# product.net
KiCad netlist of a schematic drawn in EAGLE
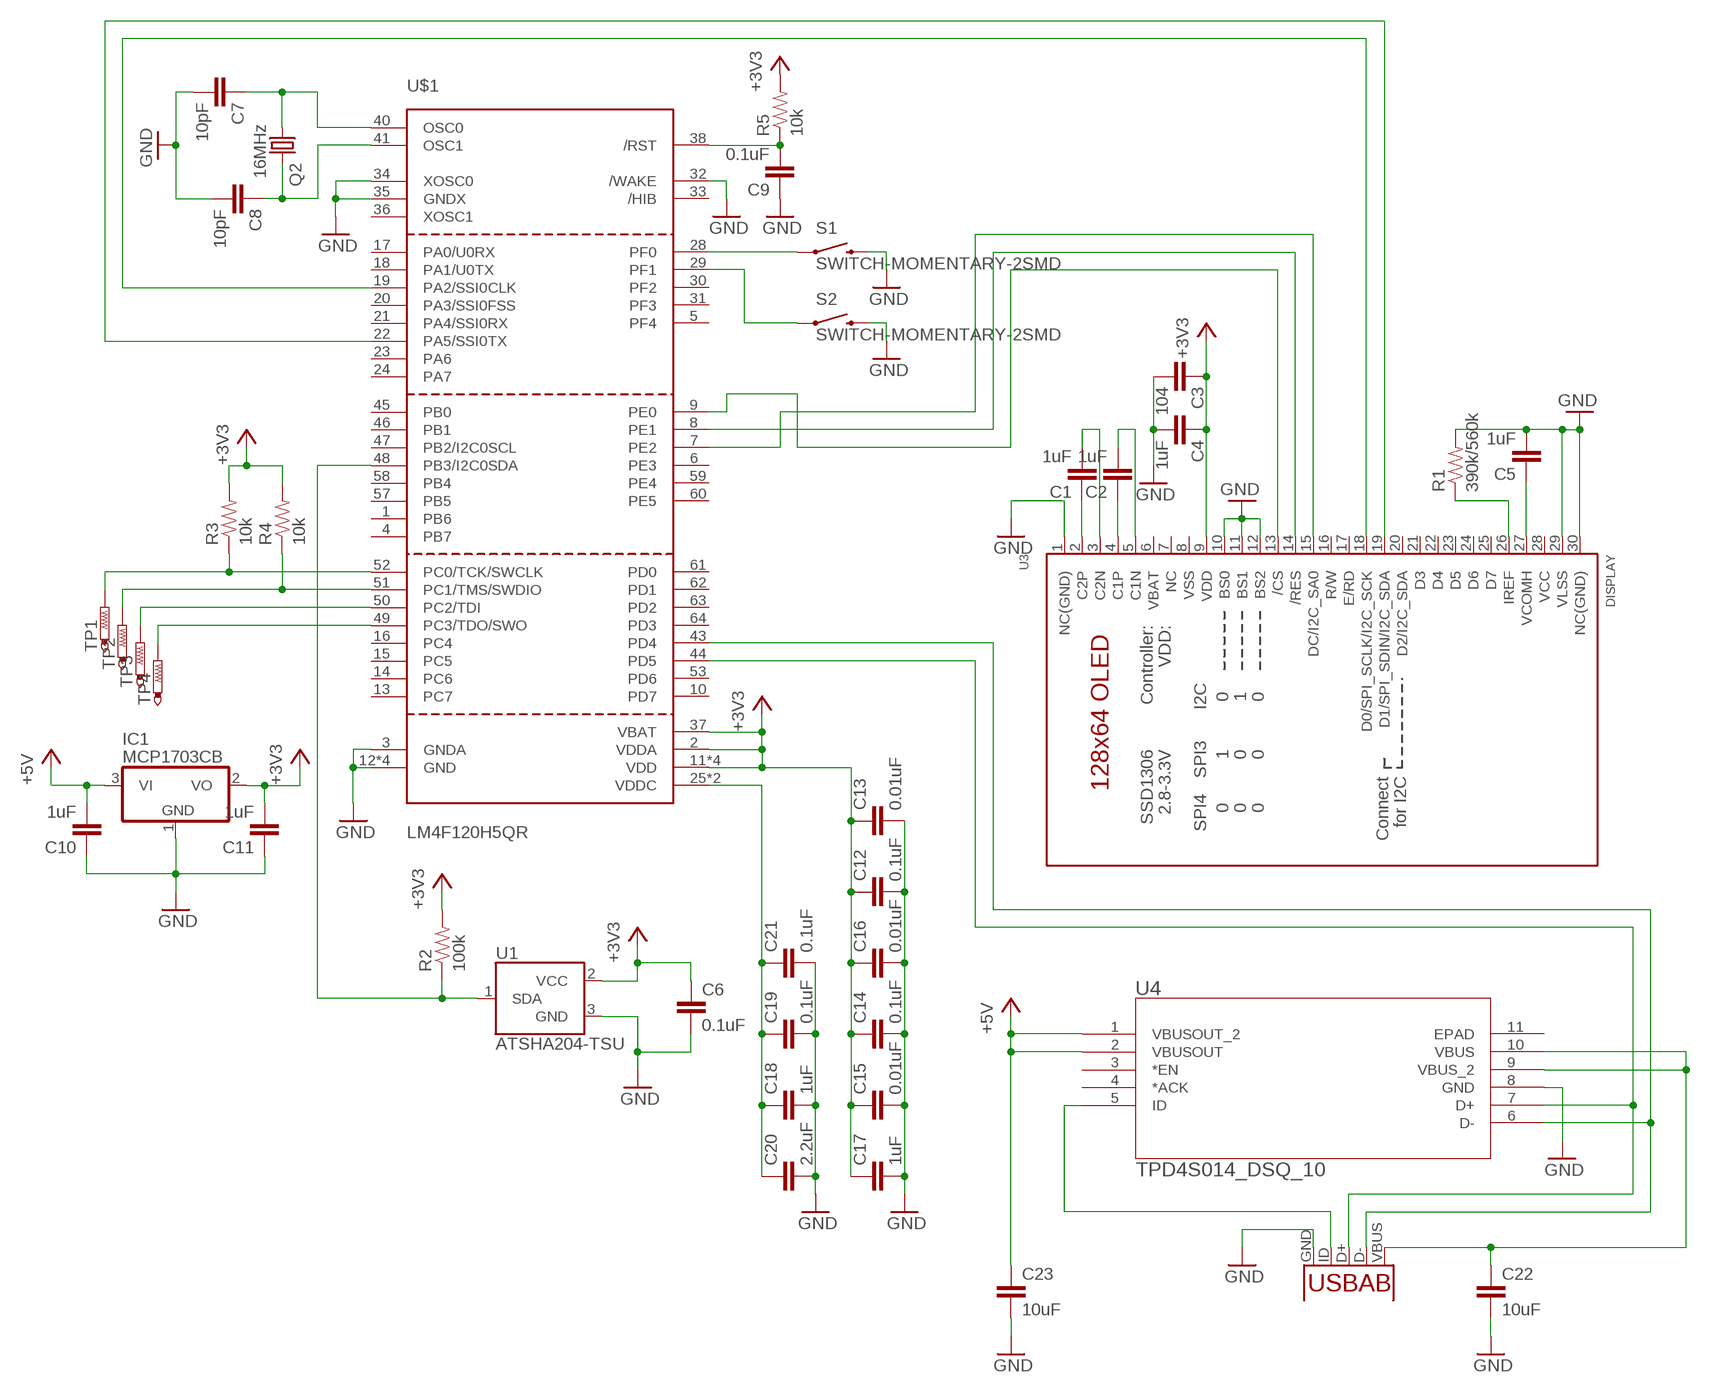
[diagram p0: schematic, sheet 1]

(export (version "E")
  (design (tool "Eeschema 10.0.6"))
  (components
    (comp (ref "C1")
      (value "1uF")
      (footprint "eagle-import:0402-CAP")
      (libsource (lib "eagle-import") (part "CAP0402-CAP"))
    )
    (comp (ref "C2")
      (value "1uF")
      (footprint "eagle-import:0402-CAP")
      (libsource (lib "eagle-import") (part "CAP0402-CAP"))
    )
    (comp (ref "C3")
      (value "104")
      (footprint "eagle-import:0402-CAP")
      (libsource (lib "eagle-import") (part "CAP0402-CAP"))
    )
    (comp (ref "C4")
      (value "1uF")
      (footprint "eagle-import:0402-CAP")
      (libsource (lib "eagle-import") (part "CAP0402-CAP"))
    )
    (comp (ref "C5")
      (value "1uF")
      (footprint "eagle-import:0402-CAP")
      (libsource (lib "eagle-import") (part "CAP0402-CAP"))
    )
    (comp (ref "C6")
      (value "0.1uF")
      (footprint "eagle-import:0402-CAP")
      (libsource (lib "eagle-import") (part "CAP0402-CAP"))
    )
    (comp (ref "C7")
      (value "10pF")
      (footprint "eagle-import:0402-CAP")
      (libsource (lib "eagle-import") (part "CAP0402-CAP"))
    )
    (comp (ref "C8")
      (value "10pF")
      (footprint "eagle-import:0402-CAP")
      (libsource (lib "eagle-import") (part "CAP0402-CAP"))
    )
    (comp (ref "C9")
      (value "0.1uF")
      (footprint "eagle-import:0402-CAP")
      (libsource (lib "eagle-import") (part "CAP0402-CAP"))
    )
    (comp (ref "C10")
      (value "1uF")
      (footprint "eagle-import:0402-CAP")
      (libsource (lib "eagle-import") (part "CAP0402-CAP"))
    )
    (comp (ref "C11")
      (value "1uF")
      (footprint "eagle-import:0402-CAP")
      (libsource (lib "eagle-import") (part "CAP0402-CAP"))
    )
    (comp (ref "C12")
      (value "0.1uF")
      (footprint "eagle-import:0402-CAP")
      (libsource (lib "eagle-import") (part "CAP0402-CAP"))
    )
    (comp (ref "C13")
      (value "0.01uF")
      (footprint "eagle-import:0402-CAP")
      (libsource (lib "eagle-import") (part "CAP0402-CAP"))
    )
    (comp (ref "C14")
      (value "0.1uF")
      (footprint "eagle-import:0402-CAP")
      (libsource (lib "eagle-import") (part "CAP0402-CAP"))
    )
    (comp (ref "C15")
      (value "0.01uF")
      (footprint "eagle-import:0402-CAP")
      (libsource (lib "eagle-import") (part "CAP0402-CAP"))
    )
    (comp (ref "C16")
      (value "0.01uF")
      (footprint "eagle-import:0402-CAP")
      (libsource (lib "eagle-import") (part "CAP0402-CAP"))
    )
    (comp (ref "C17")
      (value "1uF")
      (footprint "eagle-import:0402-CAP")
      (libsource (lib "eagle-import") (part "CAP0402-CAP"))
    )
    (comp (ref "C18")
      (value "1uF")
      (footprint "eagle-import:0402-CAP")
      (libsource (lib "eagle-import") (part "CAP0402-CAP"))
    )
    (comp (ref "C19")
      (value "0.1uF")
      (footprint "eagle-import:0402-CAP")
      (libsource (lib "eagle-import") (part "CAP0402-CAP"))
    )
    (comp (ref "C20")
      (value "2.2uF")
      (footprint "eagle-import:0402-CAP")
      (libsource (lib "eagle-import") (part "CAP0402-CAP"))
    )
    (comp (ref "C21")
      (value "0.1uF")
      (footprint "eagle-import:0402-CAP")
      (libsource (lib "eagle-import") (part "CAP0402-CAP"))
    )
    (comp (ref "C22")
      (value "10uF")
      (footprint "eagle-import:0402-CAP")
      (libsource (lib "eagle-import") (part "CAP0402-CAP"))
    )
    (comp (ref "C23")
      (value "10uF")
      (footprint "eagle-import:0402-CAP")
      (libsource (lib "eagle-import") (part "CAP0402-CAP"))
    )
    (comp (ref "IC1")
      (value "MCP1703CB")
      (footprint "eagle-import:SOT23")
      (libsource (lib "eagle-import") (part "MCP1703CB"))
    )
    (comp (ref "Q2")
      (value "16MHz")
      (footprint "eagle-import:CTS406")
      (libsource (lib "eagle-import") (part "CRYSTALCTS406"))
    )
    (comp (ref "R1")
      (value "390k/560k")
      (footprint "eagle-import:0402-RES")
      (libsource (lib "eagle-import") (part "RESISTOR0402-RES"))
    )
    (comp (ref "R2")
      (value "100k")
      (footprint "eagle-import:0402-RES")
      (libsource (lib "eagle-import") (part "RESISTOR0402-RES"))
    )
    (comp (ref "R3")
      (value "10k")
      (footprint "eagle-import:0402-RES")
      (libsource (lib "eagle-import") (part "RESISTOR0402-RES"))
    )
    (comp (ref "R4")
      (value "10k")
      (footprint "eagle-import:0402-RES")
      (libsource (lib "eagle-import") (part "RESISTOR0402-RES"))
    )
    (comp (ref "R5")
      (value "10k")
      (footprint "eagle-import:0402-RES")
      (libsource (lib "eagle-import") (part "RESISTOR0402-RES"))
    )
    (comp (ref "S1")
      (value "SWITCH-MOMENTARY-2SMD")
      (footprint "eagle-import:TACTILE_SWITCH_SMD")
      (libsource (lib "eagle-import") (part "SWITCH-MOMENTARY-2SMD"))
    )
    (comp (ref "S2")
      (value "SWITCH-MOMENTARY-2SMD")
      (footprint "eagle-import:TACTILE_SWITCH_SMD")
      (libsource (lib "eagle-import") (part "SWITCH-MOMENTARY-2SMD"))
    )
    (comp (ref "TP1")
      (value "PTR1TP10R")
      (footprint "eagle-import:TP10R")
      (libsource (lib "eagle-import") (part "PTR1TP10R"))
    )
    (comp (ref "TP2")
      (value "PTR1TP10R")
      (footprint "eagle-import:TP10R")
      (libsource (lib "eagle-import") (part "PTR1TP10R"))
    )
    (comp (ref "TP3")
      (value "PTR1TP10R")
      (footprint "eagle-import:TP10R")
      (libsource (lib "eagle-import") (part "PTR1TP10R"))
    )
    (comp (ref "TP4")
      (value "PTR1TP10R")
      (footprint "eagle-import:TP10R")
      (libsource (lib "eagle-import") (part "PTR1TP10R"))
    )
    (comp (ref "U$1")
      (value "LM4F120H5QR")
      (footprint "eagle-import:LQFP64")
      (libsource (lib "eagle-import") (part "LM4F120H5QR"))
    )
    (comp (ref "U1")
      (value "ATSHA204-TSU")
      (footprint "eagle-import:SOT23-3")
      (libsource (lib "eagle-import") (part "ATSHA204-TSU"))
    )
    (comp (ref "U2")
      (value "USB")
      (footprint "eagle-import:USB-AB-MICRO-SMD")
      (libsource (lib "eagle-import") (part "USB-AB"))
    )
    (comp (ref "U3")
      (value "DISPLAY")
      (footprint "eagle-import:UG-2864HSWEG01_0.96IN_WRAPAROUND")
      (libsource (lib "eagle-import") (part "DISP_OLED_UG-2864HSWEG010.96{dblquote}"))
    )
    (comp (ref "U4")
      (value "TPD4S014_DSQ_10")
      (footprint "eagle-import:DSQ10_1P5X0P9")
      (libsource (lib "eagle-import") (part "TPD4S014_DSQ_10"))
    )
  )
  (nets
    (net (code "1") (name "+3V3") (class "Default")
      (node (ref "C11") (pin "2") (pinfunction "2_2") (pintype "passive"))
      (node (ref "C12") (pin "1") (pinfunction "1_1") (pintype "passive"))
      (node (ref "C13") (pin "1") (pinfunction "1_1") (pintype "passive"))
      (node (ref "C14") (pin "1") (pinfunction "1_1") (pintype "passive"))
      (node (ref "C15") (pin "1") (pinfunction "1_1") (pintype "passive"))
      (node (ref "C16") (pin "1") (pinfunction "1_1") (pintype "passive"))
      (node (ref "C17") (pin "1") (pinfunction "1_1") (pintype "passive"))
      (node (ref "C3") (pin "1") (pinfunction "1_1") (pintype "passive"))
      (node (ref "C4") (pin "1") (pinfunction "1_1") (pintype "passive"))
      (node (ref "C6") (pin "1") (pinfunction "1_1") (pintype "passive"))
      (node (ref "IC1") (pin "2") (pinfunction "VO_2") (pintype "passive"))
      (node (ref "R2") (pin "2") (pinfunction "2_2") (pintype "passive"))
      (node (ref "R3") (pin "2") (pinfunction "2_2") (pintype "passive"))
      (node (ref "R4") (pin "2") (pinfunction "2_2") (pintype "passive"))
      (node (ref "R5") (pin "2") (pinfunction "2_2") (pintype "passive"))
      (node (ref "U$1") (pin "11") (pinfunction "VDD_11") (pintype "power_in"))
      (node (ref "U$1") (pin "2") (pinfunction "VDDA_2") (pintype "power_in"))
      (node (ref "U$1") (pin "26") (pinfunction "VDD_26") (pintype "power_in"))
      (node (ref "U$1") (pin "37") (pinfunction "VBAT_37") (pintype "power_in"))
      (node (ref "U$1") (pin "42") (pinfunction "VDD_42") (pintype "power_in"))
      (node (ref "U$1") (pin "54") (pinfunction "VDD_54") (pintype "power_in"))
      (node (ref "U1") (pin "2") (pinfunction "VCC_2") (pintype "bidirectional"))
      (node (ref "U3") (pin "9") (pinfunction "VDD_9") (pintype "power_in"))
    )
    (net (code "2") (name "+5V") (class "Default")
      (node (ref "C10") (pin "2") (pinfunction "2_2") (pintype "passive"))
      (node (ref "C23") (pin "1") (pinfunction "1_1") (pintype "passive"))
      (node (ref "IC1") (pin "3") (pinfunction "VI_3") (pintype "input"))
      (node (ref "U4") (pin "1") (pinfunction "VBUSOUT_2_1") (pintype "passive"))
      (node (ref "U4") (pin "2") (pinfunction "VBUSOUT_2") (pintype "passive"))
    )
    (net (code "3") (name "/VCC") (class "Default")
      (node (ref "U3") (pin "28") (pinfunction "VCC_28") (pintype "power_in"))
    )
    (net (code "4") (name "/VSS") (class "Default")
      (node (ref "U3") (pin "8") (pinfunction "VSS_8") (pintype "power_in"))
    )
    (net (code "5") (name "GND") (class "Default")
      (node (ref "C10") (pin "1") (pinfunction "1_1") (pintype "passive"))
      (node (ref "C11") (pin "1") (pinfunction "1_1") (pintype "passive"))
      (node (ref "C12") (pin "2") (pinfunction "2_2") (pintype "passive"))
      (node (ref "C13") (pin "2") (pinfunction "2_2") (pintype "passive"))
      (node (ref "C14") (pin "2") (pinfunction "2_2") (pintype "passive"))
      (node (ref "C15") (pin "2") (pinfunction "2_2") (pintype "passive"))
      (node (ref "C16") (pin "2") (pinfunction "2_2") (pintype "passive"))
      (node (ref "C17") (pin "2") (pinfunction "2_2") (pintype "passive"))
      (node (ref "C18") (pin "2") (pinfunction "2_2") (pintype "passive"))
      (node (ref "C19") (pin "2") (pinfunction "2_2") (pintype "passive"))
      (node (ref "C20") (pin "2") (pinfunction "2_2") (pintype "passive"))
      (node (ref "C21") (pin "2") (pinfunction "2_2") (pintype "passive"))
      (node (ref "C22") (pin "2") (pinfunction "2_2") (pintype "passive"))
      (node (ref "C23") (pin "2") (pinfunction "2_2") (pintype "passive"))
      (node (ref "C3") (pin "2") (pinfunction "2_2") (pintype "passive"))
      (node (ref "C4") (pin "2") (pinfunction "2_2") (pintype "passive"))
      (node (ref "C5") (pin "2") (pinfunction "2_2") (pintype "passive"))
      (node (ref "C6") (pin "2") (pinfunction "2_2") (pintype "passive"))
      (node (ref "C7") (pin "2") (pinfunction "2_2") (pintype "passive"))
      (node (ref "C8") (pin "2") (pinfunction "2_2") (pintype "passive"))
      (node (ref "C9") (pin "1") (pinfunction "1_1") (pintype "passive"))
      (node (ref "IC1") (pin "1") (pinfunction "GND_1") (pintype "passive"))
      (node (ref "R1") (pin "2") (pinfunction "2_2") (pintype "passive"))
      (node (ref "S1") (pin "3") (pinfunction "2_3") (pintype "passive"))
      (node (ref "S2") (pin "3") (pinfunction "2_3") (pintype "passive"))
      (node (ref "U$1") (pin "12") (pinfunction "GND_12") (pintype "power_in"))
      (node (ref "U$1") (pin "27") (pinfunction "GND_27") (pintype "power_in"))
      (node (ref "U$1") (pin "3") (pinfunction "GNDA_3") (pintype "power_in"))
      (node (ref "U$1") (pin "32") (pinfunction "/WAKE_32") (pintype "bidirectional"))
      (node (ref "U$1") (pin "34") (pinfunction "XOSC0_34") (pintype "passive"))
      (node (ref "U$1") (pin "35") (pinfunction "GNDX_35") (pintype "power_in"))
      (node (ref "U$1") (pin "39") (pinfunction "GND_39") (pintype "power_in"))
      (node (ref "U$1") (pin "55") (pinfunction "GND_55") (pintype "power_in"))
      (node (ref "U1") (pin "3") (pinfunction "GND_3") (pintype "bidirectional"))
      (node (ref "U2") (pin "GND") (pinfunction "GND_GND") (pintype "bidirectional"))
      (node (ref "U3") (pin "1") (pinfunction "NC(GND)_1") (pintype "input"))
      (node (ref "U3") (pin "10") (pinfunction "BS0_10") (pintype "input"))
      (node (ref "U3") (pin "11") (pinfunction "BS1_11") (pintype "input"))
      (node (ref "U3") (pin "12") (pinfunction "BS2_12") (pintype "input"))
      (node (ref "U3") (pin "29") (pinfunction "VLSS_29") (pintype "power_in"))
      (node (ref "U3") (pin "30") (pinfunction "NC(GND)_30") (pintype "input"))
      (node (ref "U4") (pin "8") (pinfunction "GND_8") (pintype "passive"))
    )
    (net (code "6") (name "Net-(C18-Pad1)") (class "Default")
      (node (ref "C18") (pin "1") (pinfunction "1_1") (pintype "passive"))
      (node (ref "C19") (pin "1") (pinfunction "1_1") (pintype "passive"))
      (node (ref "C20") (pin "1") (pinfunction "1_1") (pintype "passive"))
      (node (ref "C21") (pin "1") (pinfunction "1_1") (pintype "passive"))
      (node (ref "U$1") (pin "25") (pinfunction "VDDC_25") (pintype "power_in"))
      (node (ref "U$1") (pin "56") (pinfunction "VDDC_56") (pintype "power_in"))
    )
    (net (code "7") (name "Net-(Q2-2)") (class "Default")
      (node (ref "C8") (pin "1") (pinfunction "1_1") (pintype "passive"))
      (node (ref "Q2") (pin "3") (pinfunction "2_3") (pintype "passive"))
      (node (ref "U$1") (pin "41") (pinfunction "OSC1_41") (pintype "passive"))
    )
    (net (code "8") (name "Net-(U$1-OSC0)") (class "Default")
      (node (ref "C7") (pin "1") (pinfunction "1_1") (pintype "passive"))
      (node (ref "Q2") (pin "1") (pinfunction "1_1") (pintype "passive"))
      (node (ref "U$1") (pin "40") (pinfunction "OSC0_40") (pintype "passive"))
    )
    (net (code "9") (name "Net-(U$1-PA2{slash}SSI0CLK)") (class "Default")
      (node (ref "U$1") (pin "19") (pinfunction "PA2/SSI0CLK_19") (pintype "bidirectional"))
      (node (ref "U3") (pin "18") (pinfunction "D0/SPI_SCLK/I2C_SCK_18") (pintype "bidirectional"))
    )
    (net (code "10") (name "Net-(U$1-PA5{slash}SSI0TX)") (class "Default")
      (node (ref "U$1") (pin "22") (pinfunction "PA5/SSI0TX_22") (pintype "bidirectional"))
      (node (ref "U3") (pin "19") (pinfunction "D1/SPI_SDIN/I2C_SDA_19") (pintype "bidirectional"))
    )
    (net (code "11") (name "Net-(U$1-PB3{slash}I2C0SDA)") (class "Default")
      (node (ref "R2") (pin "1") (pinfunction "1_1") (pintype "passive"))
      (node (ref "U$1") (pin "48") (pinfunction "PB3/I2C0SDA_48") (pintype "bidirectional"))
      (node (ref "U1") (pin "1") (pinfunction "SDA_1") (pintype "bidirectional"))
    )
    (net (code "12") (name "Net-(U$1-PC0{slash}TCK{slash}SWCLK)") (class "Default")
      (node (ref "R3") (pin "1") (pinfunction "1_1") (pintype "passive"))
      (node (ref "TP1") (pin "TP") (pinfunction "TP_TP") (pintype "input"))
      (node (ref "U$1") (pin "52") (pinfunction "PC0/TCK/SWCLK_52") (pintype "bidirectional"))
    )
    (net (code "13") (name "Net-(U$1-PC1{slash}TMS{slash}SWDIO)") (class "Default")
      (node (ref "R4") (pin "1") (pinfunction "1_1") (pintype "passive"))
      (node (ref "TP2") (pin "TP") (pinfunction "TP_TP") (pintype "input"))
      (node (ref "U$1") (pin "51") (pinfunction "PC1/TMS/SWDIO_51") (pintype "bidirectional"))
    )
    (net (code "14") (name "Net-(U$1-PC2{slash}TDI)") (class "Default")
      (node (ref "TP3") (pin "TP") (pinfunction "TP_TP") (pintype "input"))
      (node (ref "U$1") (pin "50") (pinfunction "PC2/TDI_50") (pintype "bidirectional"))
    )
    (net (code "15") (name "Net-(U$1-PC3{slash}TDO{slash}SWO)") (class "Default")
      (node (ref "TP4") (pin "TP") (pinfunction "TP_TP") (pintype "input"))
      (node (ref "U$1") (pin "49") (pinfunction "PC3/TDO/SWO_49") (pintype "bidirectional"))
    )
    (net (code "16") (name "Net-(U$1-PD4)") (class "Default")
      (node (ref "U$1") (pin "43") (pinfunction "PD4_43") (pintype "bidirectional"))
      (node (ref "U2") (pin "D-") (pinfunction "D-_D-") (pintype "bidirectional"))
      (node (ref "U4") (pin "6") (pinfunction "D-_6") (pintype "passive"))
    )
    (net (code "17") (name "Net-(U$1-PD5)") (class "Default")
      (node (ref "U$1") (pin "44") (pinfunction "PD5_44") (pintype "bidirectional"))
      (node (ref "U2") (pin "D+") (pinfunction "D+_D+") (pintype "bidirectional"))
      (node (ref "U4") (pin "7") (pinfunction "D+_7") (pintype "passive"))
    )
    (net (code "18") (name "Net-(U$1-PE0)") (class "Default")
      (node (ref "U$1") (pin "9") (pinfunction "PE0_9") (pintype "bidirectional"))
      (node (ref "U3") (pin "13") (pinfunction "/CS_13") (pintype "input"))
    )
    (net (code "19") (name "Net-(U$1-PE1)") (class "Default")
      (node (ref "U$1") (pin "8") (pinfunction "PE1_8") (pintype "bidirectional"))
      (node (ref "U3") (pin "14") (pinfunction "/RES_14") (pintype "input"))
    )
    (net (code "20") (name "Net-(U$1-PE2)") (class "Default")
      (node (ref "U$1") (pin "7") (pinfunction "PE2_7") (pintype "bidirectional"))
      (node (ref "U3") (pin "15") (pinfunction "DC/I2C_SA0_15") (pintype "input"))
    )
    (net (code "21") (name "Net-(U$1-PF0)") (class "Default")
      (node (ref "S1") (pin "1") (pinfunction "1_1") (pintype "passive"))
      (node (ref "U$1") (pin "28") (pinfunction "PF0_28") (pintype "bidirectional"))
    )
    (net (code "22") (name "Net-(U$1-PF1)") (class "Default")
      (node (ref "S2") (pin "1") (pinfunction "1_1") (pintype "passive"))
      (node (ref "U$1") (pin "29") (pinfunction "PF1_29") (pintype "bidirectional"))
    )
    (net (code "23") (name "Net-(U$1-{slash}RST)") (class "Default")
      (node (ref "C9") (pin "2") (pinfunction "2_2") (pintype "passive"))
      (node (ref "R5") (pin "1") (pinfunction "1_1") (pintype "passive"))
      (node (ref "U$1") (pin "38") (pinfunction "/RST_38") (pintype "bidirectional"))
    )
    (net (code "24") (name "Net-(U2-USBID)") (class "Default")
      (node (ref "U2") (pin "ID") (pinfunction "USBID_ID") (pintype "bidirectional"))
      (node (ref "U4") (pin "5") (pinfunction "ID_5") (pintype "passive"))
    )
    (net (code "25") (name "Net-(U3-C1N)") (class "Default")
      (node (ref "C2") (pin "2") (pinfunction "2_2") (pintype "passive"))
      (node (ref "U3") (pin "5") (pinfunction "C1N_5") (pintype "input"))
    )
    (net (code "26") (name "Net-(U3-C1P)") (class "Default")
      (node (ref "C2") (pin "1") (pinfunction "1_1") (pintype "passive"))
      (node (ref "U3") (pin "4") (pinfunction "C1P_4") (pintype "input"))
    )
    (net (code "27") (name "Net-(U3-C2N)") (class "Default")
      (node (ref "C1") (pin "2") (pinfunction "2_2") (pintype "passive"))
      (node (ref "U3") (pin "3") (pinfunction "C2N_3") (pintype "input"))
    )
    (net (code "28") (name "Net-(U3-C2P)") (class "Default")
      (node (ref "C1") (pin "1") (pinfunction "1_1") (pintype "passive"))
      (node (ref "U3") (pin "2") (pinfunction "C2P_2") (pintype "input"))
    )
    (net (code "29") (name "Net-(U3-IREF)") (class "Default")
      (node (ref "R1") (pin "1") (pinfunction "1_1") (pintype "passive"))
      (node (ref "U3") (pin "26") (pinfunction "IREF_26") (pintype "input"))
    )
    (net (code "30") (name "Net-(U3-VCOMH)") (class "Default")
      (node (ref "C5") (pin "1") (pinfunction "1_1") (pintype "passive"))
      (node (ref "U3") (pin "27") (pinfunction "VCOMH_27") (pintype "output"))
    )
    (net (code "31") (name "Net-(U4-VBUS)") (class "Default")
      (node (ref "C22") (pin "1") (pinfunction "1_1") (pintype "passive"))
      (node (ref "U2") (pin "VBUS") (pinfunction "VBUS_VBUS") (pintype "bidirectional"))
      (node (ref "U4") (pin "10") (pinfunction "VBUS_10") (pintype "passive"))
      (node (ref "U4") (pin "9") (pinfunction "VBUS_2_9") (pintype "passive"))
    )
    (net (code "32") (name "unconnected-(U$1-PA0{slash}U0RX-Pad17)") (class "Default")
      (node (ref "U$1") (pin "17") (pinfunction "PA0/U0RX_17") (pintype "bidirectional"))
    )
    (net (code "33") (name "unconnected-(U$1-PA1{slash}U0TX-Pad18)") (class "Default")
      (node (ref "U$1") (pin "18") (pinfunction "PA1/U0TX_18") (pintype "bidirectional"))
    )
    (net (code "34") (name "unconnected-(U$1-PA3{slash}SSI0FSS-Pad20)") (class "Default")
      (node (ref "U$1") (pin "20") (pinfunction "PA3/SSI0FSS_20") (pintype "bidirectional"))
    )
    (net (code "35") (name "unconnected-(U$1-PA4{slash}SSI0RX-Pad21)") (class "Default")
      (node (ref "U$1") (pin "21") (pinfunction "PA4/SSI0RX_21") (pintype "bidirectional"))
    )
    (net (code "36") (name "unconnected-(U$1-PA6-Pad23)") (class "Default")
      (node (ref "U$1") (pin "23") (pinfunction "PA6_23") (pintype "bidirectional"))
    )
    (net (code "37") (name "unconnected-(U$1-PA7-Pad24)") (class "Default")
      (node (ref "U$1") (pin "24") (pinfunction "PA7_24") (pintype "bidirectional"))
    )
    (net (code "38") (name "unconnected-(U$1-PB0-Pad45)") (class "Default")
      (node (ref "U$1") (pin "45") (pinfunction "PB0_45") (pintype "bidirectional"))
    )
    (net (code "39") (name "unconnected-(U$1-PB1-Pad46)") (class "Default")
      (node (ref "U$1") (pin "46") (pinfunction "PB1_46") (pintype "bidirectional"))
    )
    (net (code "40") (name "unconnected-(U$1-PB2{slash}I2C0SCL-Pad47)") (class "Default")
      (node (ref "U$1") (pin "47") (pinfunction "PB2/I2C0SCL_47") (pintype "bidirectional"))
    )
    (net (code "41") (name "unconnected-(U$1-PB4-Pad58)") (class "Default")
      (node (ref "U$1") (pin "58") (pinfunction "PB4_58") (pintype "bidirectional"))
    )
    (net (code "42") (name "unconnected-(U$1-PB5-Pad57)") (class "Default")
      (node (ref "U$1") (pin "57") (pinfunction "PB5_57") (pintype "bidirectional"))
    )
    (net (code "43") (name "unconnected-(U$1-PB6-Pad1)") (class "Default")
      (node (ref "U$1") (pin "1") (pinfunction "PB6_1") (pintype "bidirectional"))
    )
    (net (code "44") (name "unconnected-(U$1-PB7-Pad4)") (class "Default")
      (node (ref "U$1") (pin "4") (pinfunction "PB7_4") (pintype "bidirectional"))
    )
    (net (code "45") (name "unconnected-(U$1-PC4-Pad16)") (class "Default")
      (node (ref "U$1") (pin "16") (pinfunction "PC4_16") (pintype "bidirectional"))
    )
    (net (code "46") (name "unconnected-(U$1-PC5-Pad15)") (class "Default")
      (node (ref "U$1") (pin "15") (pinfunction "PC5_15") (pintype "bidirectional"))
    )
    (net (code "47") (name "unconnected-(U$1-PC6-Pad14)") (class "Default")
      (node (ref "U$1") (pin "14") (pinfunction "PC6_14") (pintype "bidirectional"))
    )
    (net (code "48") (name "unconnected-(U$1-PC7-Pad13)") (class "Default")
      (node (ref "U$1") (pin "13") (pinfunction "PC7_13") (pintype "bidirectional"))
    )
    (net (code "49") (name "unconnected-(U$1-PD0-Pad61)") (class "Default")
      (node (ref "U$1") (pin "61") (pinfunction "PD0_61") (pintype "bidirectional"))
    )
    (net (code "50") (name "unconnected-(U$1-PD1-Pad62)") (class "Default")
      (node (ref "U$1") (pin "62") (pinfunction "PD1_62") (pintype "bidirectional"))
    )
    (net (code "51") (name "unconnected-(U$1-PD2-Pad63)") (class "Default")
      (node (ref "U$1") (pin "63") (pinfunction "PD2_63") (pintype "bidirectional"))
    )
    (net (code "52") (name "unconnected-(U$1-PD3-Pad64)") (class "Default")
      (node (ref "U$1") (pin "64") (pinfunction "PD3_64") (pintype "bidirectional"))
    )
    (net (code "53") (name "unconnected-(U$1-PD6-Pad53)") (class "Default")
      (node (ref "U$1") (pin "53") (pinfunction "PD6_53") (pintype "bidirectional"))
    )
    (net (code "54") (name "unconnected-(U$1-PD7-Pad10)") (class "Default")
      (node (ref "U$1") (pin "10") (pinfunction "PD7_10") (pintype "bidirectional"))
    )
    (net (code "55") (name "unconnected-(U$1-PE3-Pad6)") (class "Default")
      (node (ref "U$1") (pin "6") (pinfunction "PE3_6") (pintype "bidirectional"))
    )
    (net (code "56") (name "unconnected-(U$1-PE4-Pad59)") (class "Default")
      (node (ref "U$1") (pin "59") (pinfunction "PE4_59") (pintype "bidirectional"))
    )
    (net (code "57") (name "unconnected-(U$1-PE5-Pad60)") (class "Default")
      (node (ref "U$1") (pin "60") (pinfunction "PE5_60") (pintype "bidirectional"))
    )
    (net (code "58") (name "unconnected-(U$1-PF2-Pad30)") (class "Default")
      (node (ref "U$1") (pin "30") (pinfunction "PF2_30") (pintype "bidirectional"))
    )
    (net (code "59") (name "unconnected-(U$1-PF3-Pad31)") (class "Default")
      (node (ref "U$1") (pin "31") (pinfunction "PF3_31") (pintype "bidirectional"))
    )
    (net (code "60") (name "unconnected-(U$1-PF4-Pad5)") (class "Default")
      (node (ref "U$1") (pin "5") (pinfunction "PF4_5") (pintype "bidirectional"))
    )
    (net (code "61") (name "unconnected-(U$1-XOSC1-Pad36)") (class "Default")
      (node (ref "U$1") (pin "36") (pinfunction "XOSC1_36") (pintype "passive"))
    )
    (net (code "62") (name "unconnected-(U$1-{slash}HIB-Pad33)") (class "Default")
      (node (ref "U$1") (pin "33") (pinfunction "/HIB_33") (pintype "bidirectional"))
    )
    (net (code "63") (name "unconnected-(U3-D2{slash}I2C_SDA-Pad20)") (class "Default")
      (node (ref "U3") (pin "20") (pinfunction "D2/I2C_SDA_20") (pintype "bidirectional"))
    )
    (net (code "64") (name "unconnected-(U3-D3-Pad21)") (class "Default")
      (node (ref "U3") (pin "21") (pinfunction "D3_21") (pintype "bidirectional"))
    )
    (net (code "65") (name "unconnected-(U3-D4-Pad22)") (class "Default")
      (node (ref "U3") (pin "22") (pinfunction "D4_22") (pintype "bidirectional"))
    )
    (net (code "66") (name "unconnected-(U3-D5-Pad23)") (class "Default")
      (node (ref "U3") (pin "23") (pinfunction "D5_23") (pintype "bidirectional"))
    )
    (net (code "67") (name "unconnected-(U3-D6-Pad24)") (class "Default")
      (node (ref "U3") (pin "24") (pinfunction "D6_24") (pintype "bidirectional"))
    )
    (net (code "68") (name "unconnected-(U3-D7-Pad25)") (class "Default")
      (node (ref "U3") (pin "25") (pinfunction "D7_25") (pintype "bidirectional"))
    )
    (net (code "69") (name "unconnected-(U3-E{slash}RD-Pad17)") (class "Default")
      (node (ref "U3") (pin "17") (pinfunction "E/RD_17") (pintype "input"))
    )
    (net (code "70") (name "unconnected-(U3-NC-Pad7)") (class "Default")
      (node (ref "U3") (pin "7") (pinfunction "NC_7") (pintype "no_connect"))
    )
    (net (code "71") (name "unconnected-(U3-R{slash}W-Pad16)") (class "Default")
      (node (ref "U3") (pin "16") (pinfunction "R/W_16") (pintype "input"))
    )
    (net (code "72") (name "unconnected-(U3-VBAT-Pad6)") (class "Default")
      (node (ref "U3") (pin "6") (pinfunction "VBAT_6") (pintype "input"))
    )
    (net (code "73") (name "unconnected-(U4-*ACK-Pad4)") (class "Default")
      (node (ref "U4") (pin "4") (pinfunction "*ACK_4") (pintype "passive"))
    )
    (net (code "74") (name "unconnected-(U4-*EN-Pad3)") (class "Default")
      (node (ref "U4") (pin "3") (pinfunction "*EN_3") (pintype "passive"))
    )
    (net (code "75") (name "unconnected-(U4-EPAD-Pad11)") (class "Default")
      (node (ref "U4") (pin "11") (pinfunction "EPAD_11") (pintype "passive"))
    )
  )
)
